# RPi_sheet.net
KiCad netlist of a schematic drawn in EasyEDA
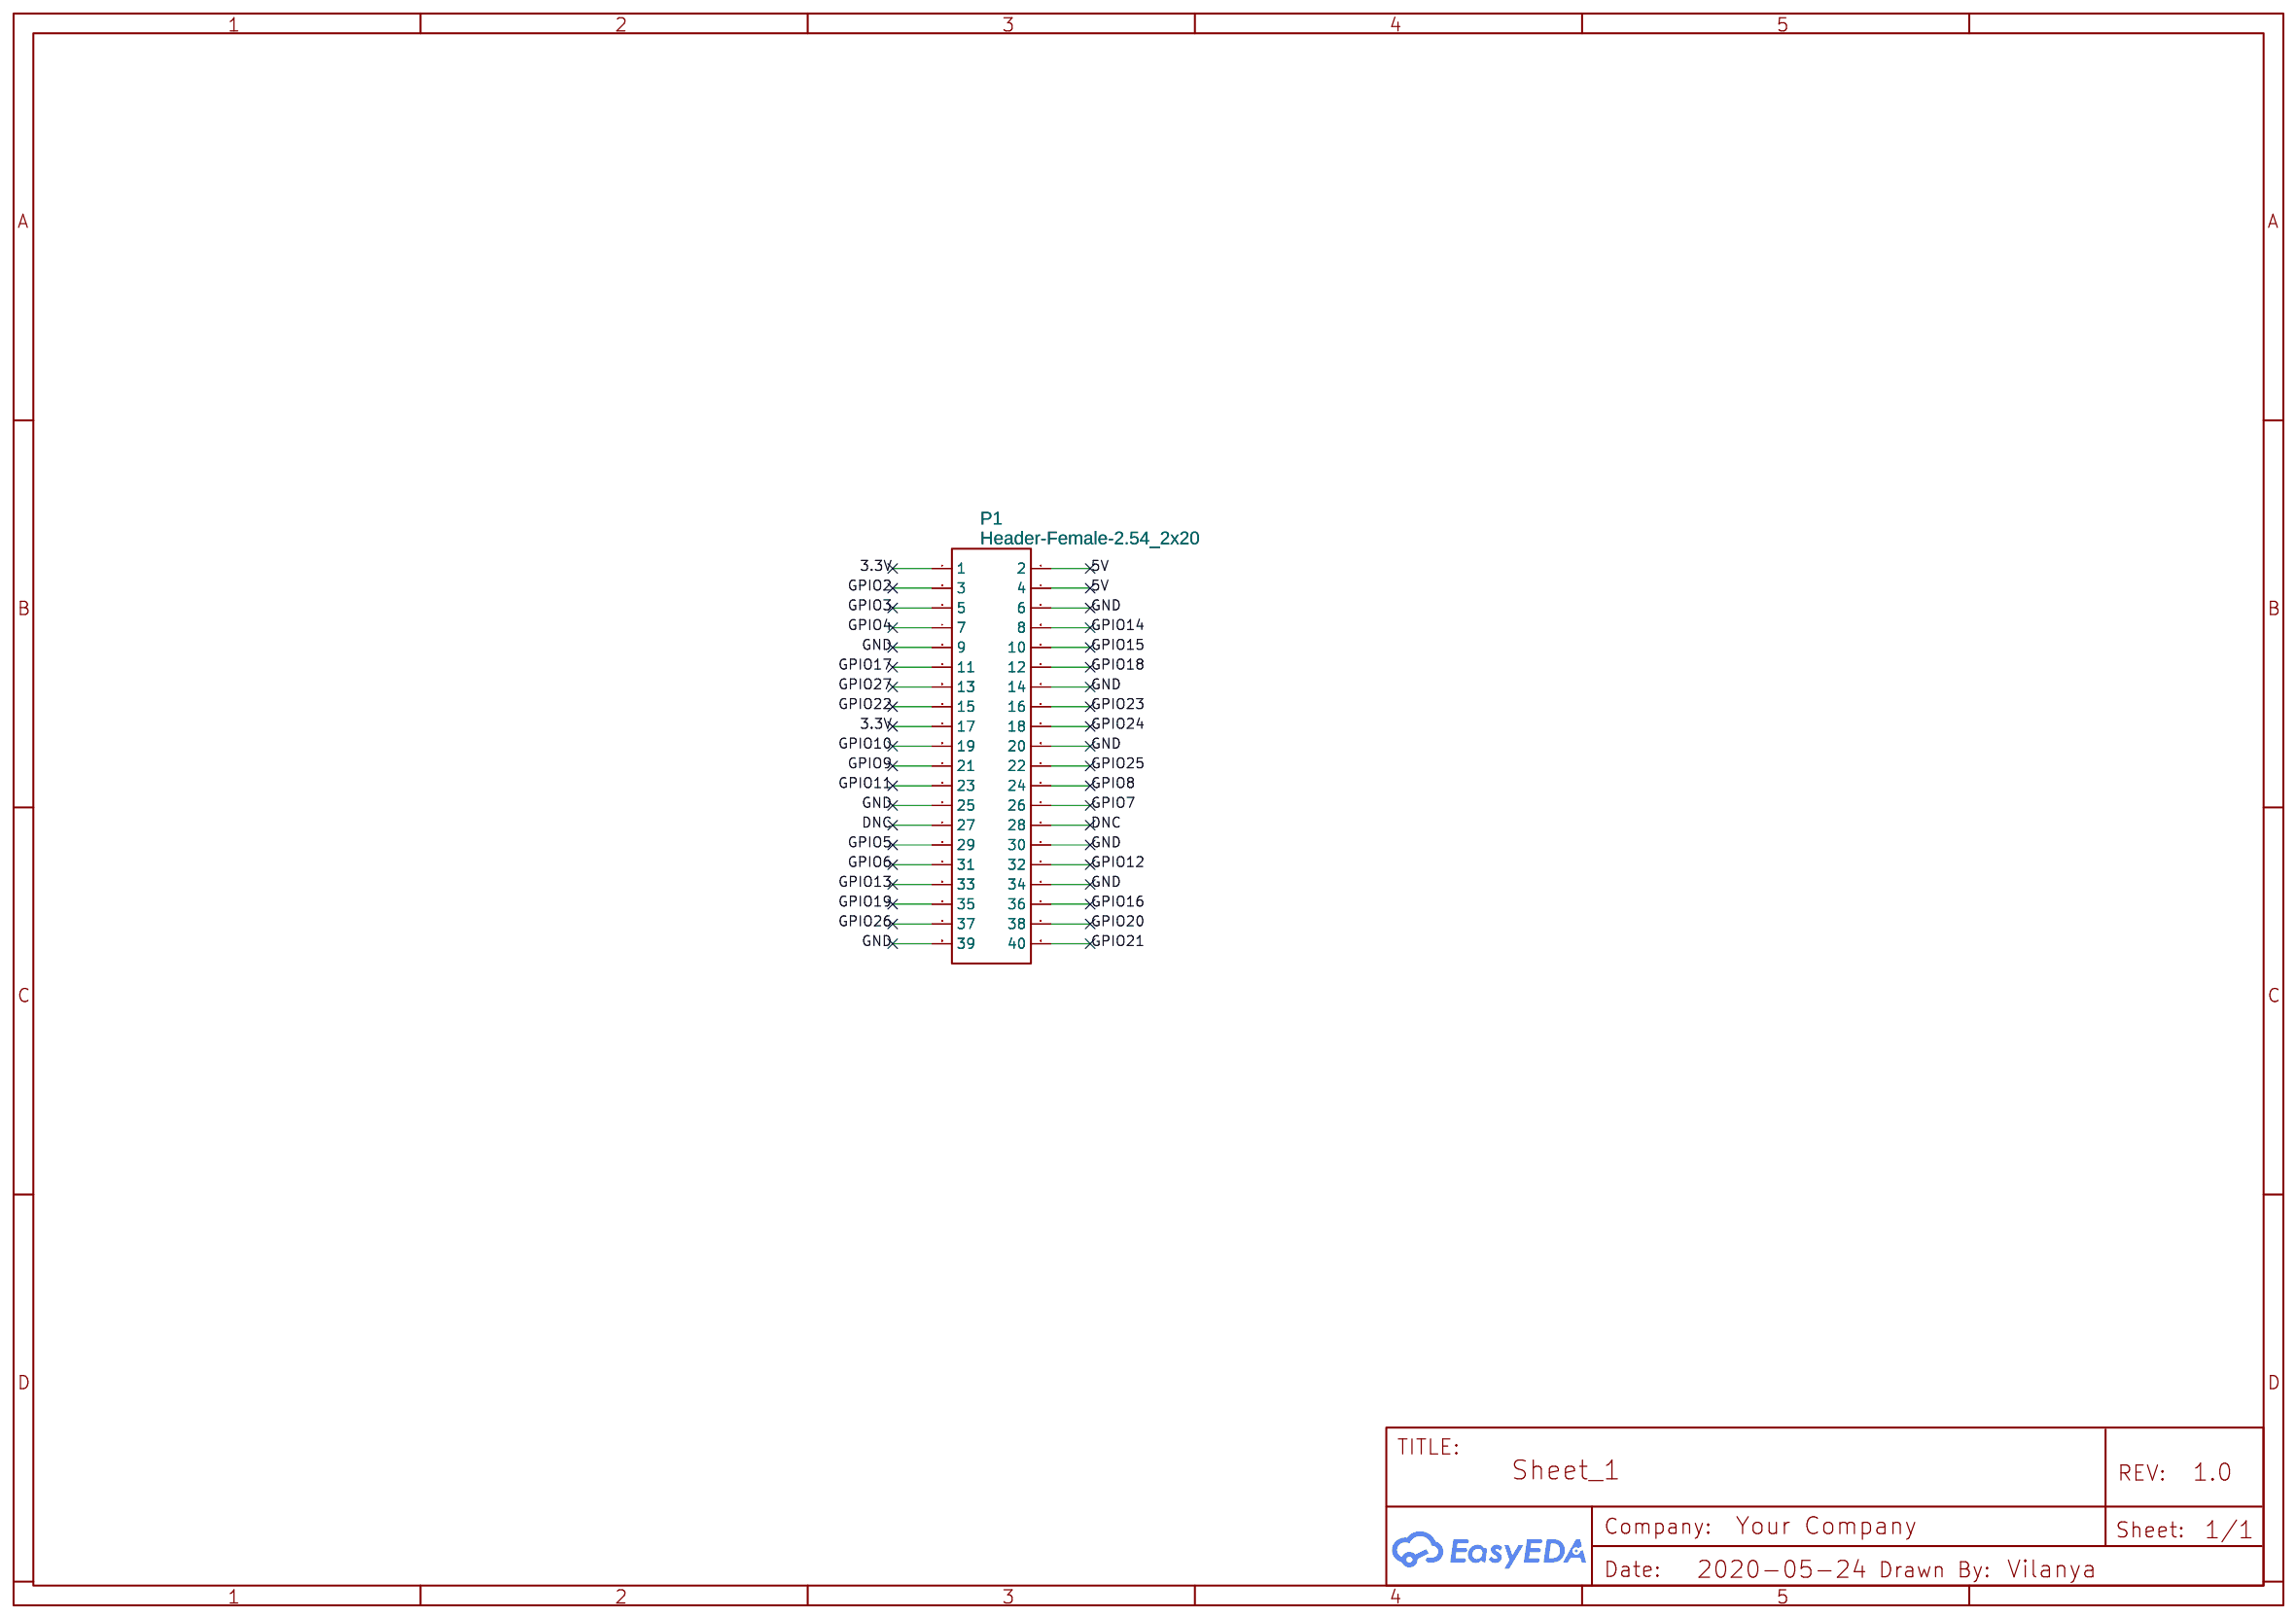
[diagram p0: schematic sheet]

(export (version "E")
  (design (tool "Eeschema 10.0.6"))
  (components
    (comp (ref "P1")
      (value "Header-Female-2.54_2x20")
      (fields
        (field (name "BOM_Manufacturer Part") "2.54mm 2*20PFemale header")
        (field (name "BOM_Supplier Part") "C50982")
      )
      (libsource (lib "") (part "Header-Female-2.54_2x20"))
    )
  )
  (nets
    (net (code "1") (name "/3.3V") (class "Default")
      (node (ref "P1") (pin "1") (pinfunction "1_1") (pintype "input"))
      (node (ref "P1") (pin "17") (pinfunction "17_17") (pintype "input"))
    )
    (net (code "2") (name "/5V") (class "Default")
      (node (ref "P1") (pin "2") (pinfunction "2_2") (pintype "input"))
      (node (ref "P1") (pin "4") (pinfunction "4_4") (pintype "input"))
    )
    (net (code "3") (name "/DNC") (class "Default")
      (node (ref "P1") (pin "27") (pinfunction "27_27") (pintype "input"))
      (node (ref "P1") (pin "28") (pinfunction "28_28") (pintype "input"))
    )
    (net (code "4") (name "/GND") (class "Default")
      (node (ref "P1") (pin "14") (pinfunction "14_14") (pintype "input"))
      (node (ref "P1") (pin "20") (pinfunction "20_20") (pintype "input"))
      (node (ref "P1") (pin "25") (pinfunction "25_25") (pintype "input"))
      (node (ref "P1") (pin "30") (pinfunction "30_30") (pintype "input"))
      (node (ref "P1") (pin "34") (pinfunction "34_34") (pintype "input"))
      (node (ref "P1") (pin "39") (pinfunction "39_39") (pintype "input"))
      (node (ref "P1") (pin "6") (pinfunction "6_6") (pintype "input"))
      (node (ref "P1") (pin "9") (pinfunction "9_9") (pintype "input"))
    )
    (net (code "5") (name "/GPIO2") (class "Default")
      (node (ref "P1") (pin "3") (pinfunction "3_3") (pintype "input+no_connect"))
    )
    (net (code "6") (name "/GPIO3") (class "Default")
      (node (ref "P1") (pin "5") (pinfunction "5_5") (pintype "input+no_connect"))
    )
    (net (code "7") (name "/GPIO4") (class "Default")
      (node (ref "P1") (pin "7") (pinfunction "7_7") (pintype "input+no_connect"))
    )
    (net (code "8") (name "/GPIO5") (class "Default")
      (node (ref "P1") (pin "29") (pinfunction "29_29") (pintype "input+no_connect"))
    )
    (net (code "9") (name "/GPIO6") (class "Default")
      (node (ref "P1") (pin "31") (pinfunction "31_31") (pintype "input+no_connect"))
    )
    (net (code "10") (name "/GPIO7") (class "Default")
      (node (ref "P1") (pin "26") (pinfunction "26_26") (pintype "input+no_connect"))
    )
    (net (code "11") (name "/GPIO8") (class "Default")
      (node (ref "P1") (pin "24") (pinfunction "24_24") (pintype "input+no_connect"))
    )
    (net (code "12") (name "/GPIO9") (class "Default")
      (node (ref "P1") (pin "21") (pinfunction "21_21") (pintype "input+no_connect"))
    )
    (net (code "13") (name "/GPIO10") (class "Default")
      (node (ref "P1") (pin "19") (pinfunction "19_19") (pintype "input+no_connect"))
    )
    (net (code "14") (name "/GPIO11") (class "Default")
      (node (ref "P1") (pin "23") (pinfunction "23_23") (pintype "input+no_connect"))
    )
    (net (code "15") (name "/GPIO12") (class "Default")
      (node (ref "P1") (pin "32") (pinfunction "32_32") (pintype "input+no_connect"))
    )
    (net (code "16") (name "/GPIO13") (class "Default")
      (node (ref "P1") (pin "33") (pinfunction "33_33") (pintype "input+no_connect"))
    )
    (net (code "17") (name "/GPIO14") (class "Default")
      (node (ref "P1") (pin "8") (pinfunction "8_8") (pintype "input+no_connect"))
    )
    (net (code "18") (name "/GPIO15") (class "Default")
      (node (ref "P1") (pin "10") (pinfunction "10_10") (pintype "input+no_connect"))
    )
    (net (code "19") (name "/GPIO16") (class "Default")
      (node (ref "P1") (pin "36") (pinfunction "36_36") (pintype "input+no_connect"))
    )
    (net (code "20") (name "/GPIO17") (class "Default")
      (node (ref "P1") (pin "11") (pinfunction "11_11") (pintype "input+no_connect"))
    )
    (net (code "21") (name "/GPIO18") (class "Default")
      (node (ref "P1") (pin "12") (pinfunction "12_12") (pintype "input+no_connect"))
    )
    (net (code "22") (name "/GPIO19") (class "Default")
      (node (ref "P1") (pin "35") (pinfunction "35_35") (pintype "input+no_connect"))
    )
    (net (code "23") (name "/GPIO20") (class "Default")
      (node (ref "P1") (pin "38") (pinfunction "38_38") (pintype "input+no_connect"))
    )
    (net (code "24") (name "/GPIO21") (class "Default")
      (node (ref "P1") (pin "40") (pinfunction "40_40") (pintype "input+no_connect"))
    )
    (net (code "25") (name "/GPIO22") (class "Default")
      (node (ref "P1") (pin "15") (pinfunction "15_15") (pintype "input+no_connect"))
    )
    (net (code "26") (name "/GPIO23") (class "Default")
      (node (ref "P1") (pin "16") (pinfunction "16_16") (pintype "input+no_connect"))
    )
    (net (code "27") (name "/GPIO24") (class "Default")
      (node (ref "P1") (pin "18") (pinfunction "18_18") (pintype "input+no_connect"))
    )
    (net (code "28") (name "/GPIO25") (class "Default")
      (node (ref "P1") (pin "22") (pinfunction "22_22") (pintype "input+no_connect"))
    )
    (net (code "29") (name "/GPIO26") (class "Default")
      (node (ref "P1") (pin "37") (pinfunction "37_37") (pintype "input+no_connect"))
    )
    (net (code "30") (name "/GPIO27") (class "Default")
      (node (ref "P1") (pin "13") (pinfunction "13_13") (pintype "input+no_connect"))
    )
  )
)
